# F4AIR.net
KiCad netlist of a schematic drawn in Altium Designer
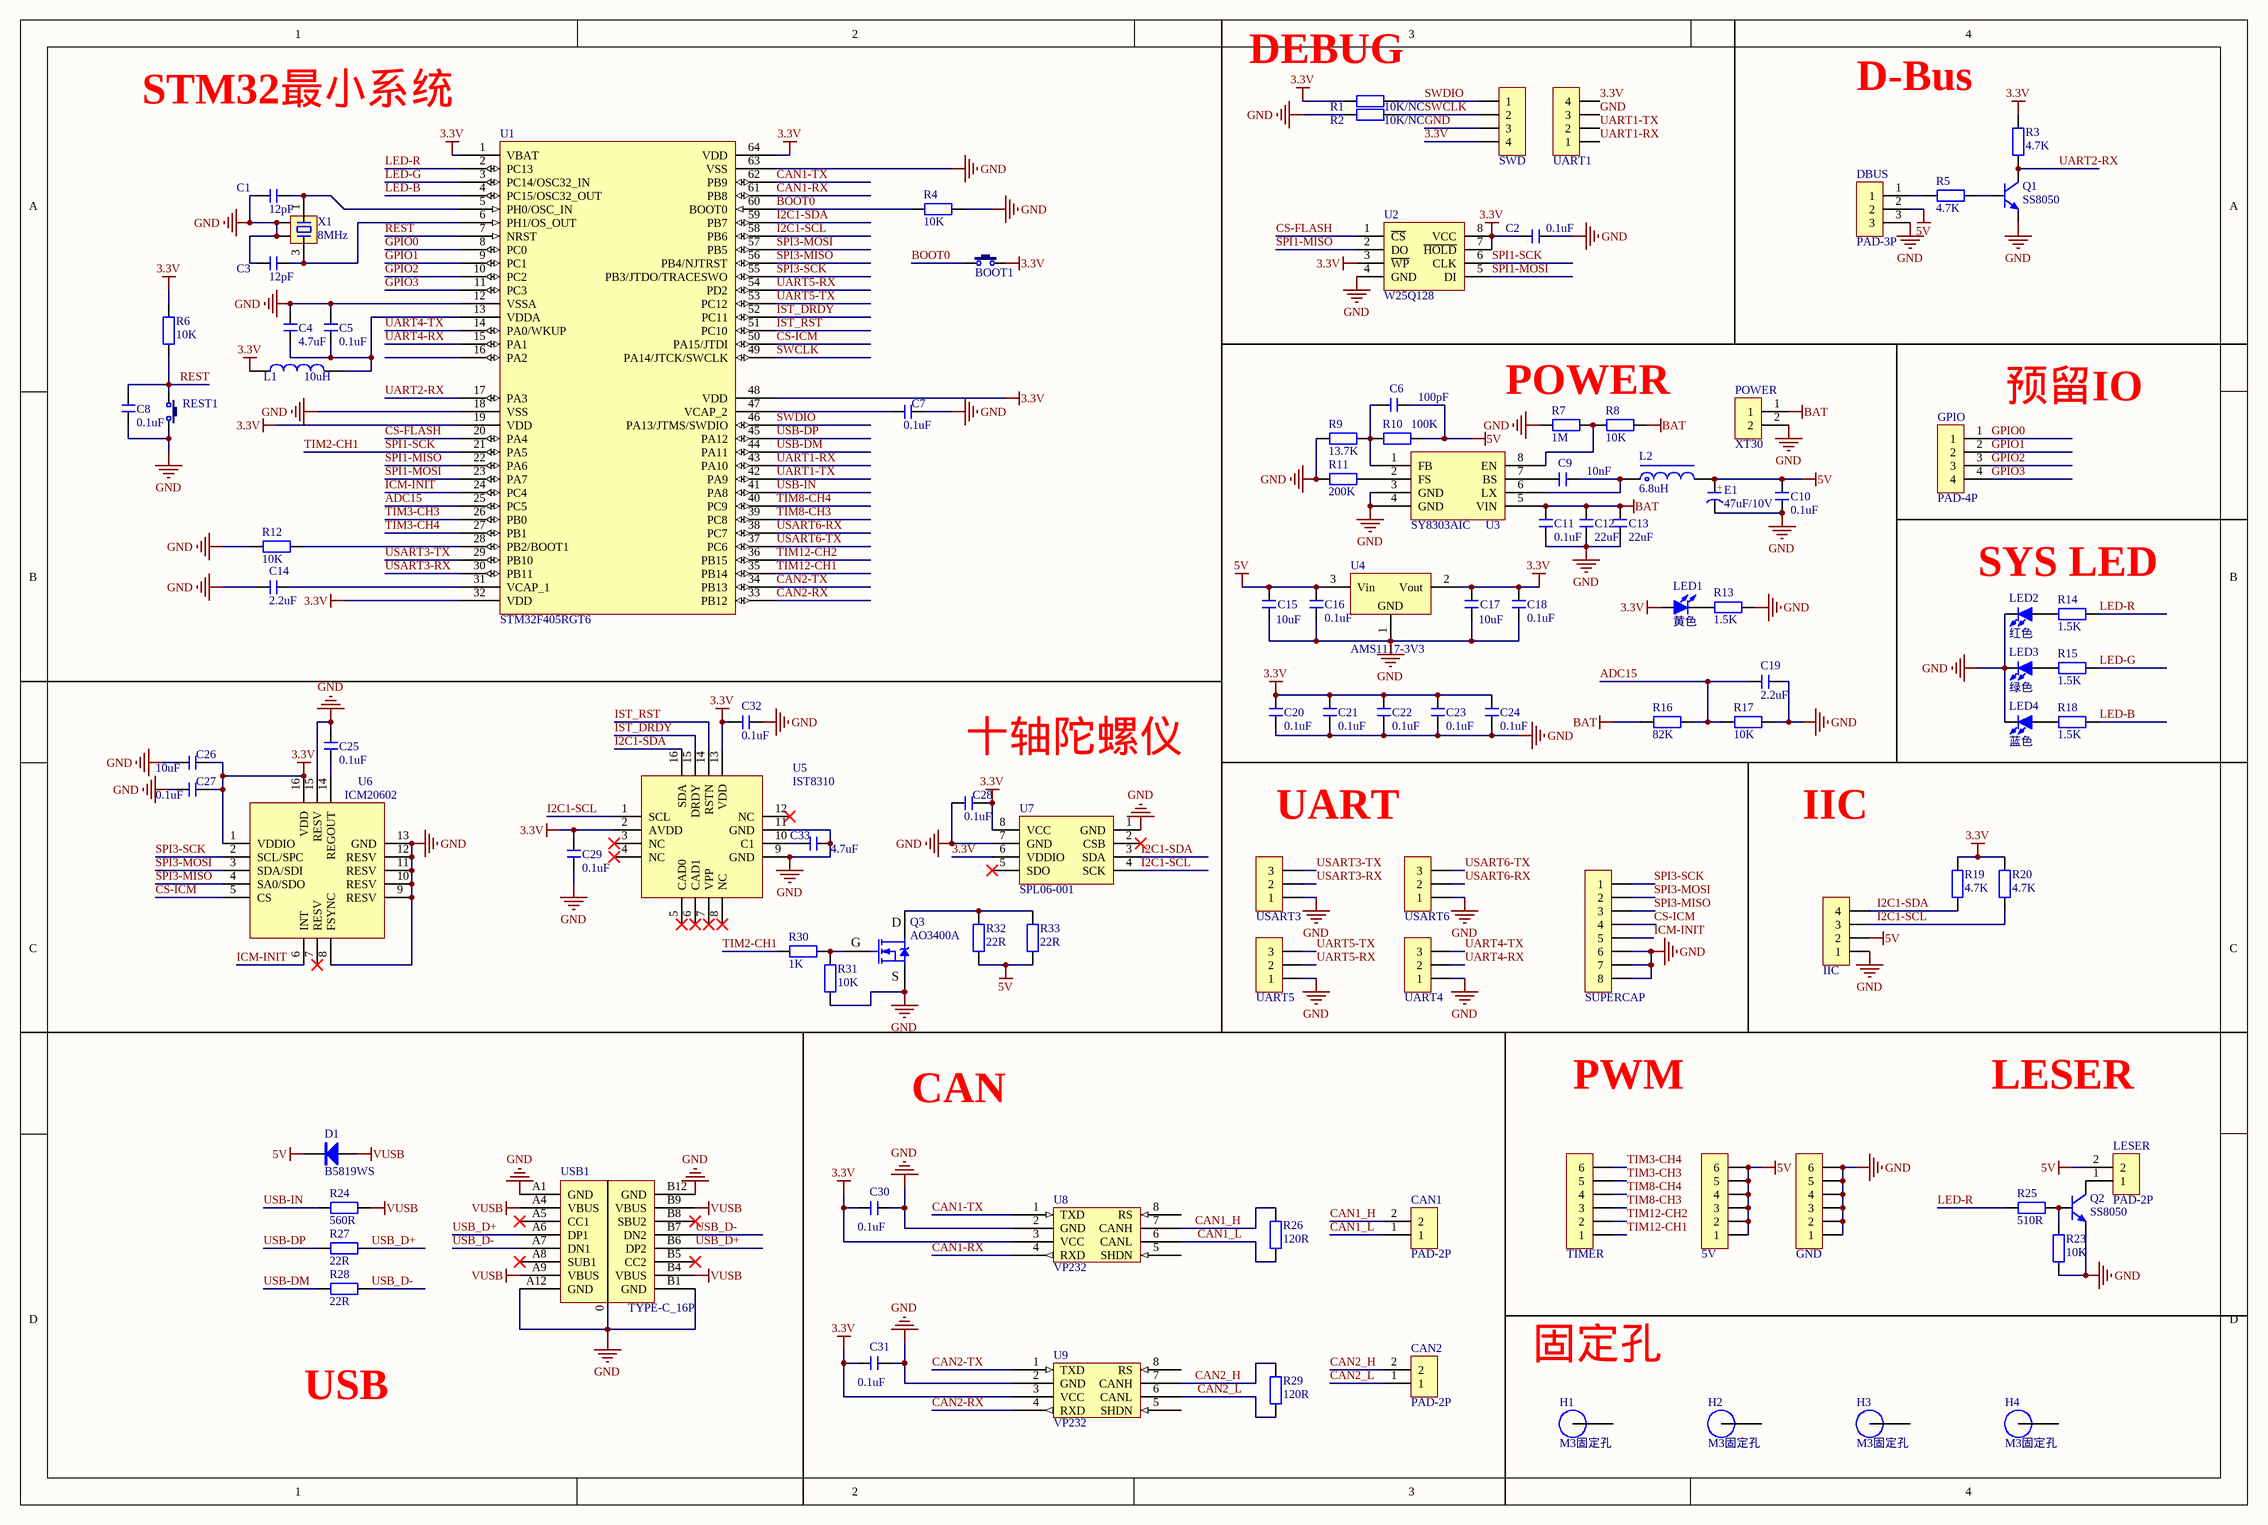
[diagram p0: F4AIR.SchDoc]

(export (version "E")
  (design (tool "Eeschema 10.0.6"))
  (components
    (comp (ref "5V")
      (value "HDR-1X6")
      (footprint "HDR2.54-LI-6P")
      (description "6P接插件")
      (libsource (lib "*") (part "Header 6"))
    )
    (comp (ref "BOOT1")
      (value "3x6x5")
      (footprint "TSW SMD-3*6*5")
      (description "3x6轻触开关")
      (libsource (lib "") (part "TSW 3x6_1"))
    )
    (comp (ref "C1")
      (value "12pF")
      (footprint "C 0603_M")
      (description "无极性贴片电容")
      (libsource (lib "Schlib1") (part "C"))
    )
    (comp (ref "C2")
      (value "0.1uF")
      (footprint "C 0603_M")
      (description "无极性贴片电容")
      (libsource (lib "Schlib") (part "C"))
    )
    (comp (ref "C3")
      (value "12pF")
      (footprint "C 0603_M")
      (description "无极性贴片电容")
      (libsource (lib "Schlib1") (part "C"))
    )
    (comp (ref "C4")
      (value "4.7uF")
      (footprint "C 0603_M")
      (description "无极性贴片电容")
      (libsource (lib "Schlib1") (part "C"))
    )
    (comp (ref "C5")
      (value "0.1uF")
      (footprint "C 0603_M")
      (description "无极性贴片电容")
      (libsource (lib "Schlib1") (part "C"))
    )
    (comp (ref "C6")
      (value "100pF")
      (footprint "C 0603_M")
      (description "无极性贴片电容")
      (libsource (lib "Schlib1") (part "C"))
    )
    (comp (ref "C7")
      (value "0.1uF")
      (footprint "C 0603_M")
      (description "无极性贴片电容")
      (libsource (lib "Schlib1") (part "C"))
    )
    (comp (ref "C8")
      (value "0.1uF")
      (footprint "C 0603_M")
      (description "无极性贴片电容")
      (libsource (lib "Schlib1") (part "C"))
    )
    (comp (ref "C9")
      (value "10nF")
      (footprint "C 0603_M")
      (description "无极性贴片电容")
      (libsource (lib "Schlib1") (part "C"))
    )
    (comp (ref "C10")
      (value "0.1uF")
      (footprint "C 0603_M")
      (description "无极性贴片电容")
      (libsource (lib "Schlib1") (part "C"))
    )
    (comp (ref "C11")
      (value "0.1uF")
      (footprint "C 0603_M")
      (description "无极性贴片电容")
      (libsource (lib "Schlib1") (part "C"))
    )
    (comp (ref "C12")
      (value "22uF")
      (footprint "C 1210_M")
      (description "无极性贴片电容")
      (libsource (lib "核心板v2") (part "C"))
    )
    (comp (ref "C13")
      (value "22uF")
      (footprint "C 1210_M")
      (description "无极性贴片电容")
      (libsource (lib "核心板v2") (part "C"))
    )
    (comp (ref "C14")
      (value "2.2uF")
      (footprint "C 0603_M")
      (description "无极性贴片电容")
      (libsource (lib "Schlib1") (part "C"))
    )
    (comp (ref "C15")
      (value "10uF")
      (footprint "C 0805_M")
      (description "无极性贴片电容")
      (libsource (lib "altium-import") (part "root_1_C_"))
    )
    (comp (ref "C16")
      (value "0.1uF")
      (footprint "C 0603_M")
      (description "无极性贴片电容")
      (libsource (lib "Schlib1") (part "C"))
    )
    (comp (ref "C17")
      (value "10uF")
      (footprint "C 0805_M")
      (description "无极性贴片电容")
      (libsource (lib "altium-import") (part "root_1_C_"))
    )
    (comp (ref "C18")
      (value "0.1uF")
      (footprint "C 0603_M")
      (description "无极性贴片电容")
      (libsource (lib "Schlib1") (part "C"))
    )
    (comp (ref "C19")
      (value "2.2uF")
      (footprint "C 0603_M")
      (description "无极性贴片电容")
      (libsource (lib "Schlib") (part "C"))
    )
    (comp (ref "C20")
      (value "0.1uF")
      (footprint "C 0603_M")
      (description "无极性贴片电容")
      (libsource (lib "Schlib1") (part "C"))
    )
    (comp (ref "C21")
      (value "0.1uF")
      (footprint "C 0603_M")
      (description "无极性贴片电容")
      (libsource (lib "Schlib1") (part "C"))
    )
    (comp (ref "C22")
      (value "0.1uF")
      (footprint "C 0603_M")
      (description "无极性贴片电容")
      (libsource (lib "Schlib1") (part "C"))
    )
    (comp (ref "C23")
      (value "0.1uF")
      (footprint "C 0603_M")
      (description "无极性贴片电容")
      (libsource (lib "Schlib1") (part "C"))
    )
    (comp (ref "C24")
      (value "0.1uF")
      (footprint "C 0603_M")
      (description "无极性贴片电容")
      (libsource (lib "Schlib1") (part "C"))
    )
    (comp (ref "C25")
      (value "0.1uF")
      (footprint "C 0603_M")
      (description "无极性贴片电容")
      (libsource (lib "Schlib1") (part "C"))
    )
    (comp (ref "C26")
      (value "10uF")
      (footprint "C 0805_M")
      (description "无极性贴片电容")
      (libsource (lib "Schlib1") (part "C"))
    )
    (comp (ref "C27")
      (value "0.1uF")
      (footprint "C 0603_M")
      (description "无极性贴片电容")
      (libsource (lib "Schlib1") (part "C"))
    )
    (comp (ref "C28")
      (value "0.1uF")
      (footprint "C 0603_M")
      (description "无极性贴片电容")
      (libsource (lib "Schlib1") (part "C"))
    )
    (comp (ref "C29")
      (value "0.1uF")
      (footprint "C 0603_M")
      (description "无极性贴片电容")
      (libsource (lib "Schlib1") (part "C"))
    )
    (comp (ref "C30")
      (value "0.1uF")
      (footprint "C 0603_M")
      (description "无极性贴片电容")
      (libsource (lib "Schlib1") (part "C"))
    )
    (comp (ref "C31")
      (value "0.1uF")
      (footprint "C 0603_M")
      (description "无极性贴片电容")
      (libsource (lib "Schlib1") (part "C"))
    )
    (comp (ref "C32")
      (value "0.1uF")
      (footprint "C 0603_M")
      (description "无极性贴片电容")
      (libsource (lib "Schlib1") (part "C"))
    )
    (comp (ref "C33")
      (value "4.7uF")
      (footprint "C 0603_M")
      (description "无极性贴片电容")
      (libsource (lib "Schlib1") (part "C"))
    )
    (comp (ref "CAN1") (value "PAD-2P") (footprint "MX 1.25-WS-2P") (libsource (lib "") (part "PAD-2P_1")))
    (comp (ref "CAN2") (value "PAD-2P") (footprint "MX 1.25-WS-2P") (libsource (lib "") (part "PAD-2P_1")))
    (comp (ref "D1")
      (value "B5819WS")
      (footprint "SOD-323")
      (description "肖特基二极管")
      (libsource (lib "Schlib") (part "SS54"))
    )
    (comp (ref "DBUS") (value "PAD-3P") (footprint "HDR2.54-WI-3P") (libsource (lib "F4AIR") (part "PAD-3P")))
    (comp (ref "E1")
      (value "47uF/10V")
      (footprint "CD A(3216)")
      (description "贴片钽电容")
      (libsource (lib "核心板v2") (part "C-CD"))
    )
    (comp (ref "GND")
      (value "HDR-1X6")
      (footprint "HDR2.54-LI-6P")
      (description "6P接插件")
      (libsource (lib "*") (part "Header 6"))
    )
    (comp (ref "GPIO") (value "PAD-4P") (footprint "PAD-1.25-4P") (libsource (lib "F4AIR") (part "PAD-4P")))
    (comp (ref "H1")
      (value "M3固定孔")
      (footprint "M3x4_N")
      (description "铜柱孔")
      (libsource (lib "F4AIR") (part "M3"))
    )
    (comp (ref "H2")
      (value "M3固定孔")
      (footprint "M3x4_N")
      (description "铜柱孔")
      (libsource (lib "F4AIR") (part "M3"))
    )
    (comp (ref "H3")
      (value "M3固定孔")
      (footprint "M3x4_N")
      (description "铜柱孔")
      (libsource (lib "F4AIR") (part "M3"))
    )
    (comp (ref "H4")
      (value "M3固定孔")
      (footprint "M3x4_N")
      (description "铜柱孔")
      (libsource (lib "F4AIR") (part "M3"))
    )
    (comp (ref "IIC")
      (value "HDR-1X4")
      (footprint "HDR2.54-LI-4P")
      (description "HDR 2.54 -4P")
      (libsource (lib "核心板v2") (part "HDR 2.54 -4P_1"))
    )
    (comp (ref "L1")
      (value "10uH")
      (footprint "L 0603")
      (description "小功率贴片电感")
      (libsource (lib "Schlib1") (part "L"))
    )
    (comp (ref "L2")
      (value "6.8uH")
      (footprint "L-SMD-0630")
      (description "贴片功率电感")
      (libsource (lib "核心板v2") (part "L-CD"))
    )
    (comp (ref "LED1")
      (value "黄色")
      (footprint "LED 0603Y")
      (description "贴片LED")
      (libsource (lib "核心板v2") (part "LED-SMD"))
    )
    (comp (ref "LED2")
      (value "红色")
      (footprint "LED 0603R")
      (description "贴片LED")
      (libsource (lib "核心板v2") (part "LED-SMD"))
    )
    (comp (ref "LED3")
      (value "绿色")
      (footprint "LED 0603G")
      (description "贴片LED")
      (libsource (lib "核心板v2") (part "LED-SMD"))
    )
    (comp (ref "LED4")
      (value "蓝色")
      (footprint "LED 0603B")
      (description "贴片LED")
      (libsource (lib "核心板v2") (part "LED-SMD"))
    )
    (comp (ref "LESER") (value "PAD-2P") (footprint "MX 1.25-WS-2P") (libsource (lib "") (part "PAD-2P_1")))
    (comp (ref "POWER") (value "XT30") (footprint "XT30-L") (libsource (lib "F4AIR") (part "PAD-2P")))
    (comp (ref "Q1")
      (value "SS8050")
      (footprint "SOT23-3M")
      (description "高频放大-NPN型")
      (libsource (lib "Schlib1") (part "8050-SMD"))
    )
    (comp (ref "Q2")
      (value "SS8050")
      (footprint "SOT23-3M")
      (description "高频放大-NPN型")
      (libsource (lib "核心板v2") (part "8050-SMD"))
    )
    (comp (ref "Q3") (value "AO3400A") (footprint "SOT23-3M") (libsource (lib "F4AIR") (part "AO3400A")))
    (comp (ref "R1")
      (value "10K/NC")
      (footprint "R 0603_M")
      (description "贴片电阻")
      (libsource (lib "Schlib1") (part "R"))
    )
    (comp (ref "R2")
      (value "10K/NC")
      (footprint "R 0603_M")
      (description "贴片电阻")
      (libsource (lib "Schlib1") (part "R"))
    )
    (comp (ref "R3")
      (value "4.7K")
      (footprint "R 0603_M")
      (description "贴片电阻")
      (libsource (lib "Schlib1") (part "R"))
    )
    (comp (ref "R4")
      (value "10K")
      (footprint "R 0603_M")
      (description "贴片电阻")
      (libsource (lib "Schlib1") (part "R"))
    )
    (comp (ref "R5")
      (value "4.7K")
      (footprint "R 0603_M")
      (description "贴片电阻")
      (libsource (lib "Schlib1") (part "R"))
    )
    (comp (ref "R6")
      (value "10K")
      (footprint "R 0603_M")
      (description "贴片电阻")
      (libsource (lib "Schlib1") (part "R"))
    )
    (comp (ref "R7")
      (value "1M")
      (footprint "R 0603_M")
      (description "贴片电阻")
      (libsource (lib "altium-import") (part "root_2_R_"))
    )
    (comp (ref "R8")
      (value "10K")
      (footprint "R 0603_M")
      (description "贴片电阻")
      (libsource (lib "altium-import") (part "root_2_R_"))
    )
    (comp (ref "R9")
      (value "13.7K")
      (footprint "R 0603_M")
      (description "贴片电阻")
      (libsource (lib "altium-import") (part "root_2_R_"))
    )
    (comp (ref "R10")
      (value "100K")
      (footprint "R 0603_M")
      (description "贴片电阻")
      (libsource (lib "altium-import") (part "root_2_R_"))
    )
    (comp (ref "R11")
      (value "200K")
      (footprint "R 0603_M")
      (description "贴片电阻")
      (libsource (lib "altium-import") (part "root_2_R_"))
    )
    (comp (ref "R12")
      (value "10K")
      (footprint "R 0603_M")
      (description "贴片电阻")
      (libsource (lib "Schlib1") (part "R"))
    )
    (comp (ref "R13")
      (value "1.5K")
      (footprint "R 0603_M")
      (description "贴片电阻")
      (libsource (lib "核心板v2") (part "R"))
    )
    (comp (ref "R14")
      (value "1.5K")
      (footprint "R 0603_M")
      (description "贴片电阻")
      (libsource (lib "核心板v2") (part "R"))
    )
    (comp (ref "R15")
      (value "1.5K")
      (footprint "R 0603_M")
      (description "贴片电阻")
      (libsource (lib "核心板v2") (part "R"))
    )
    (comp (ref "R16")
      (value "82K")
      (footprint "R 0603_M")
      (description "贴片电阻")
      (libsource (lib "Schlib") (part "R"))
    )
    (comp (ref "R17")
      (value "10K")
      (footprint "R 0603_M")
      (description "贴片电阻")
      (libsource (lib "Schlib") (part "R"))
    )
    (comp (ref "R18")
      (value "1.5K")
      (footprint "R 0603_M")
      (description "贴片电阻")
      (libsource (lib "核心板v2") (part "R"))
    )
    (comp (ref "R19")
      (value "4.7K")
      (footprint "R 0603_M")
      (description "贴片电阻")
      (libsource (lib "altium-import") (part "root_3_R_"))
    )
    (comp (ref "R20")
      (value "4.7K")
      (footprint "R 0603_M")
      (description "贴片电阻")
      (libsource (lib "altium-import") (part "root_1_R_"))
    )
    (comp (ref "R23")
      (value "10K")
      (footprint "R 0603_M")
      (description "贴片电阻")
      (libsource (lib "核心板v2") (part "R"))
    )
    (comp (ref "R24")
      (value "560R")
      (footprint "R 0603_M")
      (description "贴片电阻")
      (libsource (lib "Schlib1") (part "R"))
    )
    (comp (ref "R25")
      (value "510R")
      (footprint "R 0603_M")
      (description "贴片电阻")
      (libsource (lib "核心板v2") (part "R"))
    )
    (comp (ref "R26")
      (value "120R")
      (footprint "R 0603_M")
      (description "贴片电阻")
      (libsource (lib "altium-import") (part "root_1_R_"))
    )
    (comp (ref "R27")
      (value "22R")
      (footprint "R 0603_M")
      (description "贴片电阻")
      (libsource (lib "Schlib") (part "R"))
    )
    (comp (ref "R28")
      (value "22R")
      (footprint "R 0603_M")
      (description "贴片电阻")
      (libsource (lib "Schlib") (part "R"))
    )
    (comp (ref "R29")
      (value "120R")
      (footprint "R 0603_M")
      (description "贴片电阻")
      (libsource (lib "altium-import") (part "root_1_R_"))
    )
    (comp (ref "R30")
      (value "1K")
      (footprint "R 0603_M")
      (description "贴片电阻")
      (libsource (lib "F4AIR") (part "R"))
    )
    (comp (ref "R31")
      (value "10K")
      (footprint "R 0603_M")
      (description "贴片电阻")
      (libsource (lib "F4AIR") (part "R"))
    )
    (comp (ref "R32")
      (value "22R")
      (footprint "R 0603_M")
      (description "贴片电阻")
      (libsource (lib "F4AIR") (part "R"))
    )
    (comp (ref "R33")
      (value "22R")
      (footprint "R 0603_M")
      (description "贴片电阻")
      (libsource (lib "F4AIR") (part "R"))
    )
    (comp (ref "REST1")
      (value "3x6x5")
      (footprint "TSW SMD-3*6*5")
      (description "3x6轻触开关")
      (libsource (lib "Schlib1") (part "TSW 3x6"))
    )
    (comp (ref "SUPERCAP")
      (value "HDR-1X8")
      (footprint "MX 1.25-WS-6P")
      (description "HDR 2.54 -8P")
      (libsource (lib "cap") (part "HDR 2.54 -8P"))
    )
    (comp (ref "SWD")
      (value "HDR-1X4")
      (footprint "MX 1.25-WS-4P")
      (description "MX 1.25 -4P")
      (libsource (lib "Schlib1") (part "MX 1.25 -4P"))
    )
    (comp (ref "TIMER")
      (value "HDR-1X6")
      (footprint "HDR2.54-LI-6P")
      (description "6P接插件")
      (libsource (lib "*") (part "Header 6"))
    )
    (comp (ref "U1")
      (value "STM32F405RGT6")
      (footprint "LQFP64")
      (libsource (lib "Schlib") (part "STM32F405RGT6"))
    )
    (comp (ref "U2")
      (value "W25Q128")
      (footprint "SOP8_M - 208mil")
      (libsource (lib "Schlib") (part "W25Q128"))
    )
    (comp (ref "U3")
      (value "SY8303AIC")
      (footprint "SOT23-8")
      (description "DCDC降压芯片")
      (libsource (lib "核心板v2") (part "SY8303AIC"))
    )
    (comp (ref "U4")
      (value "AMS1117-3V3")
      (footprint "SOT-89")
      (description "三端稳压芯片")
      (libsource (lib "F4AIR") (part "AMS1117"))
    )
    (comp (ref "U5")
      (value "IST8310")
      (footprint "LGA16 3x3")
      (description "三轴电子罗盘")
      (libsource (lib "F4AIR") (part "IST8310"))
    )
    (comp (ref "U6") (value "ICM20602") (footprint "LGA16") (libsource (lib "Schlib1") (part "ICM20602")))
    (comp (ref "U7") (value "SPL06-001") (footprint "LGA08") (libsource (lib "Schlib1") (part "SPL06")))
    (comp (ref "U8")
      (value "VP232")
      (footprint "SOP8_M")
      (description "CAN芯片")
      (libsource (lib "核心板v2") (part "MAX3051EKA+T"))
    )
    (comp (ref "U9")
      (value "VP232")
      (footprint "SOP8_M")
      (description "CAN芯片")
      (libsource (lib "核心板v2") (part "MAX3051EKA+T"))
    )
    (comp (ref "UART1")
      (value "HDR-1X4")
      (footprint "MX 1.25-WS-4P")
      (description "HDR 2.54 -4P")
      (libsource (lib "核心板v2") (part "HDR 2.54 -4P_1"))
    )
    (comp (ref "UART4")
      (value "HDR-1X3")
      (footprint "MX 1.25-WS-3P")
      (description "HDR 2.54 -3P")
      (libsource (lib "Schlib1") (part "HDR 2.54 -3P"))
    )
    (comp (ref "UART5")
      (value "HDR-1X3")
      (footprint "MX 1.25-WS-3P")
      (description "HDR 2.54 -3P")
      (libsource (lib "Schlib1") (part "HDR 2.54 -3P"))
    )
    (comp (ref "USART3")
      (value "HDR-1X3")
      (footprint "MX 1.25-WS-3P")
      (description "HDR 2.54 -3P")
      (libsource (lib "Schlib1") (part "HDR 2.54 -3P"))
    )
    (comp (ref "USART6")
      (value "HDR-1X3")
      (footprint "MX 1.25-WS-3P")
      (description "HDR 2.54 -3P")
      (libsource (lib "Schlib1") (part "HDR 2.54 -3P"))
    )
    (comp (ref "USB1")
      (value "TYPE-C_16P")
      (footprint "Type-C_16p")
      (libsource (lib "Schlib") (part "TYPE-C_16P"))
    )
    (comp (ref "X1")
      (value "8MHz")
      (footprint "OSC 3225-4P")
      (description "4脚无源晶振")
      (libsource (lib "Schlib1") (part "XTAL-4P"))
    )
  )
  (nets
    (net (code "1") (name "/ADC15") (class "Default")
      (node (ref "C19") (pin "1") (pinfunction "1_1") (pintype "passive"))
      (node (ref "R16") (pin "2") (pinfunction "2_2") (pintype "passive"))
      (node (ref "R17") (pin "1") (pinfunction "1_1") (pintype "passive"))
      (node (ref "U1") (pin "25") (pinfunction "PC5_25") (pintype "bidirectional"))
    )
    (net (code "2") (name "/BOOT0") (class "Default")
      (node (ref "BOOT1") (pin "1") (pinfunction "1_1") (pintype "passive"))
      (node (ref "R4") (pin "1") (pinfunction "1_1") (pintype "passive"))
      (node (ref "U1") (pin "60") (pinfunction "BOOT0_60") (pintype "input"))
    )
    (net (code "3") (name "/CAN1-RX") (class "Default")
      (node (ref "U1") (pin "61") (pinfunction "PB8_61") (pintype "bidirectional"))
      (node (ref "U8") (pin "4") (pinfunction "RXD_4") (pintype "output"))
    )
    (net (code "4") (name "/CAN1-TX") (class "Default")
      (node (ref "U1") (pin "62") (pinfunction "PB9_62") (pintype "bidirectional"))
      (node (ref "U8") (pin "1") (pinfunction "TXD_1") (pintype "input"))
    )
    (net (code "5") (name "/CAN1_H") (class "Default")
      (node (ref "CAN1") (pin "2") (pinfunction "2_2") (pintype "passive"))
      (node (ref "R26") (pin "2") (pinfunction "2_2") (pintype "passive"))
      (node (ref "U8") (pin "7") (pinfunction "CANH_7") (pintype "passive"))
    )
    (net (code "6") (name "/CAN1_L") (class "Default")
      (node (ref "CAN1") (pin "1") (pinfunction "1_1") (pintype "passive"))
      (node (ref "R26") (pin "1") (pinfunction "1_1") (pintype "passive"))
      (node (ref "U8") (pin "6") (pinfunction "CANL_6") (pintype "passive"))
    )
    (net (code "7") (name "/CAN2-RX") (class "Default")
      (node (ref "U1") (pin "33") (pinfunction "PB12_33") (pintype "bidirectional"))
      (node (ref "U9") (pin "4") (pinfunction "RXD_4") (pintype "output"))
    )
    (net (code "8") (name "/CAN2-TX") (class "Default")
      (node (ref "U1") (pin "34") (pinfunction "PB13_34") (pintype "bidirectional"))
      (node (ref "U9") (pin "1") (pinfunction "TXD_1") (pintype "input"))
    )
    (net (code "9") (name "/CAN2_H") (class "Default")
      (node (ref "CAN2") (pin "2") (pinfunction "2_2") (pintype "passive"))
      (node (ref "R29") (pin "2") (pinfunction "2_2") (pintype "passive"))
      (node (ref "U9") (pin "7") (pinfunction "CANH_7") (pintype "passive"))
    )
    (net (code "10") (name "/CAN2_L") (class "Default")
      (node (ref "CAN2") (pin "1") (pinfunction "1_1") (pintype "passive"))
      (node (ref "R29") (pin "1") (pinfunction "1_1") (pintype "passive"))
      (node (ref "U9") (pin "6") (pinfunction "CANL_6") (pintype "passive"))
    )
    (net (code "11") (name "/CS-FLASH") (class "Default")
      (node (ref "U1") (pin "20") (pinfunction "PA4_20") (pintype "bidirectional"))
      (node (ref "U2") (pin "1") (pinfunction "~{CS}_1") (pintype "passive"))
    )
    (net (code "12") (name "/CS-ICM") (class "Default")
      (node (ref "SUPERCAP") (pin "4") (pinfunction "4_4") (pintype "passive"))
      (node (ref "U1") (pin "50") (pinfunction "PA15/JTDI_50") (pintype "bidirectional"))
      (node (ref "U6") (pin "5") (pinfunction "CS_5") (pintype "passive"))
    )
    (net (code "13") (name "/GPIO0") (class "Default")
      (node (ref "GPIO") (pin "1") (pinfunction "1_1") (pintype "passive"))
      (node (ref "U1") (pin "8") (pinfunction "PC0_8") (pintype "bidirectional"))
    )
    (net (code "14") (name "/GPIO1") (class "Default")
      (node (ref "GPIO") (pin "2") (pinfunction "2_2") (pintype "passive"))
      (node (ref "U1") (pin "9") (pinfunction "PC1_9") (pintype "bidirectional"))
    )
    (net (code "15") (name "/GPIO2") (class "Default")
      (node (ref "GPIO") (pin "3") (pinfunction "3_3") (pintype "passive"))
      (node (ref "U1") (pin "10") (pinfunction "PC2_10") (pintype "bidirectional"))
    )
    (net (code "16") (name "/GPIO3") (class "Default")
      (node (ref "GPIO") (pin "4") (pinfunction "4_4") (pintype "passive"))
      (node (ref "U1") (pin "11") (pinfunction "PC3_11") (pintype "bidirectional"))
    )
    (net (code "17") (name "/I2C1-SCL") (class "Default")
      (node (ref "IIC") (pin "3") (pinfunction "3_3") (pintype "passive"))
      (node (ref "R20") (pin "1") (pinfunction "1_1") (pintype "passive"))
      (node (ref "U1") (pin "58") (pinfunction "PB6_58") (pintype "bidirectional"))
      (node (ref "U5") (pin "1") (pinfunction "SCL_1") (pintype "passive"))
      (node (ref "U7") (pin "4") (pinfunction "SCK_4") (pintype "passive"))
    )
    (net (code "18") (name "/I2C1-SDA") (class "Default")
      (node (ref "IIC") (pin "4") (pinfunction "4_4") (pintype "passive"))
      (node (ref "R19") (pin "2") (pinfunction "2_2") (pintype "passive"))
      (node (ref "U1") (pin "59") (pinfunction "PB7_59") (pintype "bidirectional"))
      (node (ref "U5") (pin "16") (pinfunction "SDA_16") (pintype "passive"))
      (node (ref "U7") (pin "3") (pinfunction "SDA_3") (pintype "passive"))
    )
    (net (code "19") (name "/ICM-INIT") (class "Default")
      (node (ref "SUPERCAP") (pin "5") (pinfunction "5_5") (pintype "passive"))
      (node (ref "U1") (pin "24") (pinfunction "PC4_24") (pintype "bidirectional"))
      (node (ref "U6") (pin "6") (pinfunction "INT_6") (pintype "passive"))
    )
    (net (code "20") (name "/IST_DRDY") (class "Default")
      (node (ref "U1") (pin "52") (pinfunction "PC11_52") (pintype "bidirectional"))
      (node (ref "U5") (pin "15") (pinfunction "DRDY_15") (pintype "passive"))
    )
    (net (code "21") (name "/IST_RST") (class "Default")
      (node (ref "U1") (pin "51") (pinfunction "PC10_51") (pintype "bidirectional"))
      (node (ref "U5") (pin "14") (pinfunction "RSTN_14") (pintype "passive"))
    )
    (net (code "22") (name "/LED-B") (class "Default")
      (node (ref "R18") (pin "2") (pinfunction "2_2") (pintype "passive"))
      (node (ref "U1") (pin "4") (pinfunction "PC15/OSC32_OUT_4") (pintype "bidirectional"))
    )
    (net (code "23") (name "/LED-G") (class "Default")
      (node (ref "R15") (pin "2") (pinfunction "2_2") (pintype "passive"))
      (node (ref "U1") (pin "3") (pinfunction "PC14/OSC32_IN_3") (pintype "bidirectional"))
    )
    (net (code "24") (name "/LED-R") (class "Default")
      (node (ref "R14") (pin "2") (pinfunction "2_2") (pintype "passive"))
      (node (ref "R25") (pin "1") (pinfunction "1_1") (pintype "passive"))
      (node (ref "U1") (pin "2") (pinfunction "PC13_2") (pintype "bidirectional"))
    )
    (net (code "25") (name "/REST") (class "Default")
      (node (ref "C8") (pin "2") (pinfunction "2_2") (pintype "passive"))
      (node (ref "R6") (pin "1") (pinfunction "1_1") (pintype "passive"))
      (node (ref "REST1") (pin "1") (pinfunction "1_1") (pintype "passive"))
      (node (ref "U1") (pin "7") (pinfunction "NRST_7") (pintype "input"))
    )
    (net (code "26") (name "/SPI1-MISO") (class "Default")
      (node (ref "U1") (pin "22") (pinfunction "PA6_22") (pintype "bidirectional"))
      (node (ref "U2") (pin "2") (pinfunction "DO_2") (pintype "passive"))
    )
    (net (code "27") (name "/SPI1-MOSI") (class "Default")
      (node (ref "U1") (pin "23") (pinfunction "PA7_23") (pintype "bidirectional"))
      (node (ref "U2") (pin "5") (pinfunction "DI_5") (pintype "passive"))
    )
    (net (code "28") (name "/SPI1-SCK") (class "Default")
      (node (ref "R30") (pin "1") (pinfunction "1_1") (pintype "passive"))
      (node (ref "U1") (pin "21") (pinfunction "PA5_21") (pintype "bidirectional"))
      (node (ref "U2") (pin "6") (pinfunction "CLK_6") (pintype "passive"))
    )
    (net (code "29") (name "/SPI3-MISO") (class "Default")
      (node (ref "SUPERCAP") (pin "3") (pinfunction "3_3") (pintype "passive"))
      (node (ref "U1") (pin "56") (pinfunction "PB4/NJTRST_56") (pintype "bidirectional"))
      (node (ref "U6") (pin "4") (pinfunction "SA0/SDO_4") (pintype "passive"))
    )
    (net (code "30") (name "/SPI3-MOSI") (class "Default")
      (node (ref "SUPERCAP") (pin "2") (pinfunction "2_2") (pintype "passive"))
      (node (ref "U1") (pin "57") (pinfunction "PB5_57") (pintype "bidirectional"))
      (node (ref "U6") (pin "3") (pinfunction "SDA/SDI_3") (pintype "passive"))
    )
    (net (code "31") (name "/SPI3-SCK") (class "Default")
      (node (ref "SUPERCAP") (pin "1") (pinfunction "1_1") (pintype "passive"))
      (node (ref "U1") (pin "55") (pinfunction "PB3/JTDO/TRACESWO_55") (pintype "bidirectional"))
      (node (ref "U6") (pin "2") (pinfunction "SCL/SPC_2") (pintype "passive"))
    )
    (net (code "32") (name "/SWCLK") (class "Default")
      (node (ref "R2") (pin "2") (pinfunction "2_2") (pintype "passive"))
      (node (ref "SWD") (pin "2") (pinfunction "2_2") (pintype "passive"))
      (node (ref "U1") (pin "49") (pinfunction "PA14/JTCK/SWCLK_49") (pintype "bidirectional"))
    )
    (net (code "33") (name "/SWDIO") (class "Default")
      (node (ref "R1") (pin "2") (pinfunction "2_2") (pintype "passive"))
      (node (ref "SWD") (pin "1") (pinfunction "1_1") (pintype "passive"))
      (node (ref "U1") (pin "46") (pinfunction "PA13/JTMS/SWDIO_46") (pintype "bidirectional"))
    )
    (net (code "34") (name "/TIM3-CH3") (class "Default")
      (node (ref "TIMER") (pin "5") (pinfunction "5_5") (pintype "passive"))
      (node (ref "U1") (pin "26") (pinfunction "PB0_26") (pintype "bidirectional"))
    )
    (net (code "35") (name "/TIM3-CH4") (class "Default")
      (node (ref "TIMER") (pin "6") (pinfunction "6_6") (pintype "passive"))
      (node (ref "U1") (pin "27") (pinfunction "PB1_27") (pintype "bidirectional"))
    )
    (net (code "36") (name "/TIM8-CH3") (class "Default")
      (node (ref "TIMER") (pin "3") (pinfunction "3_3") (pintype "passive"))
      (node (ref "U1") (pin "39") (pinfunction "PC8_39") (pintype "bidirectional"))
    )
    (net (code "37") (name "/TIM8-CH4") (class "Default")
      (node (ref "TIMER") (pin "4") (pinfunction "4_4") (pintype "passive"))
      (node (ref "U1") (pin "40") (pinfunction "PC9_40") (pintype "bidirectional"))
    )
    (net (code "38") (name "/TIM12-CH1") (class "Default")
      (node (ref "TIMER") (pin "1") (pinfunction "1_1") (pintype "passive"))
      (node (ref "U1") (pin "35") (pinfunction "PB14_35") (pintype "bidirectional"))
    )
    (net (code "39") (name "/TIM12-CH2") (class "Default")
      (node (ref "TIMER") (pin "2") (pinfunction "2_2") (pintype "passive"))
      (node (ref "U1") (pin "36") (pinfunction "PB15_36") (pintype "bidirectional"))
    )
    (net (code "40") (name "/UART1-RX") (class "Default")
      (node (ref "U1") (pin "43") (pinfunction "PA10_43") (pintype "bidirectional"))
      (node (ref "UART1") (pin "1") (pinfunction "1_1") (pintype "passive"))
    )
    (net (code "41") (name "/UART1-TX") (class "Default")
      (node (ref "U1") (pin "42") (pinfunction "PA9_42") (pintype "bidirectional"))
      (node (ref "UART1") (pin "2") (pinfunction "2_2") (pintype "passive"))
    )
    (net (code "42") (name "/UART2-RX") (class "Default")
      (node (ref "Q1") (pin "3") (pinfunction "C_3") (pintype "passive"))
      (node (ref "R3") (pin "1") (pinfunction "1_1") (pintype "passive"))
      (node (ref "U1") (pin "17") (pinfunction "PA3_17") (pintype "bidirectional"))
    )
    (net (code "43") (name "/UART4-RX") (class "Default")
      (node (ref "U1") (pin "15") (pinfunction "PA1_15") (pintype "bidirectional"))
      (node (ref "UART4") (pin "2") (pinfunction "2_2") (pintype "passive"))
    )
    (net (code "44") (name "/UART4-TX") (class "Default")
      (node (ref "U1") (pin "14") (pinfunction "PA0/WKUP_14") (pintype "bidirectional"))
      (node (ref "UART4") (pin "3") (pinfunction "3_3") (pintype "passive"))
    )
    (net (code "45") (name "/UART5-RX") (class "Default")
      (node (ref "U1") (pin "54") (pinfunction "PD2_54") (pintype "bidirectional"))
      (node (ref "UART5") (pin "2") (pinfunction "2_2") (pintype "passive"))
    )
    (net (code "46") (name "/UART5-TX") (class "Default")
      (node (ref "U1") (pin "53") (pinfunction "PC12_53") (pintype "bidirectional"))
      (node (ref "UART5") (pin "3") (pinfunction "3_3") (pintype "passive"))
    )
    (net (code "47") (name "/USART3-RX") (class "Default")
      (node (ref "U1") (pin "30") (pinfunction "PB11_30") (pintype "bidirectional"))
      (node (ref "USART3") (pin "2") (pinfunction "2_2") (pintype "passive"))
    )
    (net (code "48") (name "/USART3-TX") (class "Default")
      (node (ref "U1") (pin "29") (pinfunction "PB10_29") (pintype "bidirectional"))
      (node (ref "USART3") (pin "3") (pinfunction "3_3") (pintype "passive"))
    )
    (net (code "49") (name "/USART6-RX") (class "Default")
      (node (ref "U1") (pin "38") (pinfunction "PC7_38") (pintype "bidirectional"))
      (node (ref "USART6") (pin "2") (pinfunction "2_2") (pintype "passive"))
    )
    (net (code "50") (name "/USART6-TX") (class "Default")
      (node (ref "U1") (pin "37") (pinfunction "PC6_37") (pintype "bidirectional"))
      (node (ref "USART6") (pin "3") (pinfunction "3_3") (pintype "passive"))
    )
    (net (code "51") (name "/USB-DM") (class "Default")
      (node (ref "R28") (pin "1") (pinfunction "1_1") (pintype "passive"))
      (node (ref "U1") (pin "44") (pinfunction "PA11_44") (pintype "bidirectional"))
    )
    (net (code "52") (name "/USB-DP") (class "Default")
      (node (ref "R27") (pin "1") (pinfunction "1_1") (pintype "passive"))
      (node (ref "U1") (pin "45") (pinfunction "PA12_45") (pintype "bidirectional"))
    )
    (net (code "53") (name "/USB-IN") (class "Default")
      (node (ref "R24") (pin "1") (pinfunction "1_1") (pintype "passive"))
      (node (ref "U1") (pin "41") (pinfunction "PA8_41") (pintype "bidirectional"))
    )
    (net (code "54") (name "/USB_D+") (class "Default")
      (node (ref "R27") (pin "2") (pinfunction "2_2") (pintype "passive"))
      (node (ref "USB1") (pin "A6") (pinfunction "DP1_A6") (pintype "passive"))
      (node (ref "USB1") (pin "B6") (pinfunction "DP2_B6") (pintype "passive"))
    )
    (net (code "55") (name "/USB_D-") (class "Default")
      (node (ref "R28") (pin "2") (pinfunction "2_2") (pintype "passive"))
      (node (ref "USB1") (pin "A7") (pinfunction "DN1_A7") (pintype "passive"))
      (node (ref "USB1") (pin "B7") (pinfunction "DN2_B7") (pintype "passive"))
    )
    (net (code "56") (name "3.3V") (class "Default")
      (node (ref "BOOT1") (pin "2") (pinfunction "2_2") (pintype "passive"))
      (node (ref "C17") (pin "2") (pinfunction "2_2") (pintype "passive"))
      (node (ref "C18") (pin "1") (pinfunction "1_1") (pintype "passive"))
      (node (ref "C2") (pin "1") (pinfunction "1_1") (pintype "passive"))
      (node (ref "C20") (pin "1") (pinfunction "1_1") (pintype "passive"))
      (node (ref "C21") (pin "1") (pinfunction "1_1") (pintype "passive"))
      (node (ref "C22") (pin "1") (pinfunction "1_1") (pintype "passive"))
      (node (ref "C23") (pin "1") (pinfunction "1_1") (pintype "passive"))
      (node (ref "C24") (pin "1") (pinfunction "1_1") (pintype "passive"))
      (node (ref "C26") (pin "2") (pinfunction "2_2") (pintype "passive"))
      (node (ref "C27") (pin "2") (pinfunction "2_2") (pintype "passive"))
      (node (ref "C28") (pin "2") (pinfunction "2_2") (pintype "passive"))
      (node (ref "C29") (pin "2") (pinfunction "2_2") (pintype "passive"))
      (node (ref "C30") (pin "2") (pinfunction "2_2") (pintype "passive"))
      (node (ref "C31") (pin "2") (pinfunction "2_2") (pintype "passive"))
      (node (ref "C32") (pin "2") (pinfunction "2_2") (pintype "passive"))
      (node (ref "L1") (pin "1") (pinfunction "1_1") (pintype "passive"))
      (node (ref "LED1") (pin "1") (pinfunction "A_1") (pintype "passive"))
      (node (ref "R1") (pin "1") (pinfunction "1_1") (pintype "passive"))
      (node (ref "R19") (pin "1") (pinfunction "1_1") (pintype "passive"))
      (node (ref "R20") (pin "2") (pinfunction "2_2") (pintype "passive"))
      (node (ref "R3") (pin "2") (pinfunction "2_2") (pintype "passive"))
      (node (ref "R6") (pin "2") (pinfunction "2_2") (pintype "passive"))
      (node (ref "SWD") (pin "4") (pinfunction "4_4") (pintype "passive"))
      (node (ref "U1") (pin "1") (pinfunction "VBAT_1") (pintype "power_in"))
      (node (ref "U1") (pin "19") (pinfunction "VDD_19") (pintype "power_in"))
      (node (ref "U1") (pin "32") (pinfunction "VDD_32") (pintype "power_in"))
      (node (ref "U1") (pin "48") (pinfunction "VDD_48") (pintype "power_in"))
      (node (ref "U1") (pin "64") (pinfunction "VDD_64") (pintype "power_in"))
      (node (ref "U2") (pin "3") (pinfunction "~{WP}_3") (pintype "passive"))
      (node (ref "U2") (pin "7") (pinfunction "~{HOLD}_7") (pintype "passive"))
      (node (ref "U2") (pin "8") (pinfunction "VCC_8") (pintype "passive"))
      (node (ref "U4") (pin "2") (pinfunction "Vout_2") (pintype "passive"))
      (node (ref "U5") (pin "13") (pinfunction "VDD_13") (pintype "passive"))
      (node (ref "U5") (pin "2") (pinfunction "AVDD_2") (pintype "passive"))
      (node (ref "U6") (pin "1") (pinfunction "VDDIO_1") (pintype "passive"))
      (node (ref "U6") (pin "16") (pinfunction "VDD_16") (pintype "passive"))
      (node (ref "U7") (pin "6") (pinfunction "VDDIO_6") (pintype "passive"))
      (node (ref "U7") (pin "8") (pinfunction "VCC_8") (pintype "passive"))
      (node (ref "U8") (pin "3") (pinfunction "VCC_3") (pintype "power_in"))
      (node (ref "U9") (pin "3") (pinfunction "VCC_3") (pintype "power_in"))
      (node (ref "UART1") (pin "4") (pinfunction "4_4") (pintype "passive"))
    )
    (net (code "57") (name "5V") (class "Default")
      (node (ref "5V") (pin "1") (pinfunction "1_1") (pintype "passive"))
      (node (ref "5V") (pin "2") (pinfunction "2_2") (pintype "passive"))
      (node (ref "5V") (pin "3") (pinfunction "3_3") (pintype "passive"))
      (node (ref "5V") (pin "4") (pinfunction "4_4") (pintype "passive"))
      (node (ref "5V") (pin "5") (pinfunction "5_5") (pintype "passive"))
      (node (ref "5V") (pin "6") (pinfunction "6_6") (pintype "passive"))
      (node (ref "C10") (pin "1") (pinfunction "1_1") (pintype "passive"))
      (node (ref "C15") (pin "2") (pinfunction "2_2") (pintype "passive"))
      (node (ref "C16") (pin "1") (pinfunction "1_1") (pintype "passive"))
      (node (ref "C6") (pin "1") (pinfunction "1_1") (pintype "passive"))
      (node (ref "D1") (pin "2") (pinfunction "K_2") (pintype "passive"))
      (node (ref "DBUS") (pin "2") (pinfunction "2_2") (pintype "passive"))
      (node (ref "E1") (pin "1") (pinfunction "A_1") (pintype "passive"))
      (node (ref "IIC") (pin "2") (pinfunction "2_2") (pintype "passive"))
      (node (ref "L2") (pin "2") (pinfunction "2_2") (pintype "passive"))
      (node (ref "LESER") (pin "2") (pinfunction "2_2") (pintype "passive"))
      (node (ref "R10") (pin "1") (pinfunction "1_1") (pintype "passive"))
      (node (ref "R32") (pin "1") (pinfunction "1_1") (pintype "passive"))
      (node (ref "R33") (pin "1") (pinfunction "1_1") (pintype "passive"))
      (node (ref "U4") (pin "3") (pinfunction "Vin_3") (pintype "passive"))
    )
    (net (code "58") (name "BAT") (class "Default")
      (node (ref "C11") (pin "1") (pinfunction "1_1") (pintype "passive"))
      (node (ref "C12") (pin "2") (pinfunction "2_2") (pintype "passive"))
      (node (ref "C13") (pin "2") (pinfunction "2_2") (pintype "passive"))
      (node (ref "POWER") (pin "1") (pinfunction "1_1") (pintype "passive"))
      (node (ref "R16") (pin "1") (pinfunction "1_1") (pintype "passive"))
      (node (ref "R8") (pin "1") (pinfunction "1_1") (pintype "passive"))
      (node (ref "U3") (pin "5") (pinfunction "VIN_5") (pintype "passive"))
    )
    (net (code "59") (name "GND") (class "Default")
      (node (ref "C1") (pin "1") (pinfunction "1_1") (pintype "passive"))
      (node (ref "C10") (pin "2") (pinfunction "2_2") (pintype "passive"))
      (node (ref "C11") (pin "2") (pinfunction "2_2") (pintype "passive"))
      (node (ref "C12") (pin "1") (pinfunction "1_1") (pintype "passive"))
      (node (ref "C13") (pin "1") (pinfunction "1_1") (pintype "passive"))
      (node (ref "C14") (pin "1") (pinfunction "1_1") (pintype "passive"))
      (node (ref "C15") (pin "1") (pinfunction "1_1") (pintype "passive"))
      (node (ref "C16") (pin "2") (pinfunction "2_2") (pintype "passive"))
      (node (ref "C17") (pin "1") (pinfunction "1_1") (pintype "passive"))
      (node (ref "C18") (pin "2") (pinfunction "2_2") (pintype "passive"))
      (node (ref "C19") (pin "2") (pinfunction "2_2") (pintype "passive"))
      (node (ref "C2") (pin "2") (pinfunction "2_2") (pintype "passive"))
      (node (ref "C20") (pin "2") (pinfunction "2_2") (pintype "passive"))
      (node (ref "C21") (pin "2") (pinfunction "2_2") (pintype "passive"))
      (node (ref "C22") (pin "2") (pinfunction "2_2") (pintype "passive"))
      (node (ref "C23") (pin "2") (pinfunction "2_2") (pintype "passive"))
      (node (ref "C24") (pin "2") (pinfunction "2_2") (pintype "passive"))
      (node (ref "C25") (pin "2") (pinfunction "2_2") (pintype "passive"))
      (node (ref "C26") (pin "1") (pinfunction "1_1") (pintype "passive"))
      (node (ref "C27") (pin "1") (pinfunction "1_1") (pintype "passive"))
      (node (ref "C28") (pin "1") (pinfunction "1_1") (pintype "passive"))
      (node (ref "C29") (pin "1") (pinfunction "1_1") (pintype "passive"))
      (node (ref "C3") (pin "1") (pinfunction "1_1") (pintype "passive"))
      (node (ref "C30") (pin "1") (pinfunction "1_1") (pintype "passive"))
      (node (ref "C31") (pin "1") (pinfunction "1_1") (pintype "passive"))
      (node (ref "C32") (pin "1") (pinfunction "1_1") (pintype "passive"))
      (node (ref "C33") (pin "1") (pinfunction "1_1") (pintype "passive"))
      (node (ref "C4") (pin "2") (pinfunction "2_2") (pintype "passive"))
      (node (ref "C5") (pin "2") (pinfunction "2_2") (pintype "passive"))
      (node (ref "C7") (pin "2") (pinfunction "2_2") (pintype "passive"))
      (node (ref "C8") (pin "1") (pinfunction "1_1") (pintype "passive"))
      (node (ref "DBUS") (pin "3") (pinfunction "3_3") (pintype "passive"))
      (node (ref "E1") (pin "2") (pinfunction "K_2") (pintype "passive"))
      (node (ref "GND") (pin "1") (pinfunction "1_1") (pintype "passive"))
      (node (ref "GND") (pin "2") (pinfunction "2_2") (pintype "passive"))
      (node (ref "GND") (pin "3") (pinfunction "3_3") (pintype "passive"))
      (node (ref "GND") (pin "4") (pinfunction "4_4") (pintype "passive"))
      (node (ref "GND") (pin "5") (pinfunction "5_5") (pintype "passive"))
      (node (ref "GND") (pin "6") (pinfunction "6_6") (pintype "passive"))
      (node (ref "IIC") (pin "1") (pinfunction "1_1") (pintype "passive"))
      (node (ref "LED2") (pin "2") (pinfunction "K_2") (pintype "passive"))
      (node (ref "LED3") (pin "2") (pinfunction "K_2") (pintype "passive"))
      (node (ref "LED4") (pin "2") (pinfunction "K_2") (pintype "passive"))
      (node (ref "POWER") (pin "2") (pinfunction "2_2") (pintype "passive"))
      (node (ref "Q1") (pin "2") (pinfunction "E_2") (pintype "passive"))
      (node (ref "Q2") (pin "2") (pinfunction "E_2") (pintype "passive"))
      (node (ref "Q3") (pin "2") (pinfunction "S_2") (pintype "passive"))
      (node (ref "R11") (pin "2") (pinfunction "2_2") (pintype "passive"))
      (node (ref "R12") (pin "1") (pinfunction "1_1") (pintype "passive"))
      (node (ref "R13") (pin "2") (pinfunction "2_2") (pintype "passive"))
      (node (ref "R17") (pin "2") (pinfunction "2_2") (pintype "passive"))
      (node (ref "R2") (pin "1") (pinfunction "1_1") (pintype "passive"))
      (node (ref "R23") (pin "1") (pinfunction "1_1") (pintype "passive"))
      (node (ref "R31") (pin "1") (pinfunction "1_1") (pintype "passive"))
      (node (ref "R4") (pin "2") (pinfunction "2_2") (pintype "passive"))
      (node (ref "R7") (pin "2") (pinfunction "2_2") (pintype "passive"))
      (node (ref "R9") (pin "2") (pinfunction "2_2") (pintype "passive"))
      (node (ref "REST1") (pin "2") (pinfunction "2_2") (pintype "passive"))
      (node (ref "SUPERCAP") (pin "6") (pinfunction "6_6") (pintype "passive"))
      (node (ref "SUPERCAP") (pin "7") (pinfunction "7_7") (pintype "passive"))
      (node (ref "SUPERCAP") (pin "8") (pinfunction "8_8") (pintype "passive"))
      (node (ref "SWD") (pin "3") (pinfunction "3_3") (pintype "passive"))
      (node (ref "U1") (pin "12") (pinfunction "VSSA_12") (pintype "power_in"))
      (node (ref "U1") (pin "18") (pinfunction "VSS_18") (pintype "power_in"))
      (node (ref "U1") (pin "63") (pinfunction "VSS_63") (pintype "power_in"))
      (node (ref "U2") (pin "4") (pinfunction "GND_4") (pintype "passive"))
      (node (ref "U3") (pin "3") (pinfunction "GND_3") (pintype "passive"))
      (node (ref "U3") (pin "4") (pinfunction "GND_4") (pintype "passive"))
      (node (ref "U4") (pin "1") (pinfunction "GND_1") (pintype "passive"))
      (node (ref "U5") (pin "11") (pinfunction "GND_11") (pintype "passive"))
      (node (ref "U5") (pin "9") (pinfunction "GND_9") (pintype "passive"))
      (node (ref "U6") (pin "10") (pinfunction "RESV_10") (pintype "passive"))
      (node (ref "U6") (pin "11") (pinfunction "RESV_11") (pintype "passive"))
      (node (ref "U6") (pin "12") (pinfunction "RESV_12") (pintype "passive"))
      (node (ref "U6") (pin "13") (pinfunction "GND_13") (pintype "passive"))
      (node (ref "U6") (pin "15") (pinfunction "RESV_15") (pintype "passive"))
      (node (ref "U6") (pin "8") (pinfunction "FSYNC_8") (pintype "passive"))
      (node (ref "U6") (pin "9") (pinfunction "RESV_9") (pintype "passive"))
      (node (ref "U7") (pin "1") (pinfunction "GND_1") (pintype "passive"))
      (node (ref "U7") (pin "7") (pinfunction "GND_7") (pintype "passive"))
      (node (ref "U8") (pin "2") (pinfunction "GND_2") (pintype "power_in"))
      (node (ref "U9") (pin "2") (pinfunction "GND_2") (pintype "power_in"))
      (node (ref "UART1") (pin "3") (pinfunction "3_3") (pintype "passive"))
      (node (ref "UART4") (pin "1") (pinfunction "1_1") (pintype "passive"))
      (node (ref "UART5") (pin "1") (pinfunction "1_1") (pintype "passive"))
      (node (ref "USART3") (pin "1") (pinfunction "1_1") (pintype "passive"))
      (node (ref "USART6") (pin "1") (pinfunction "1_1") (pintype "passive"))
      (node (ref "USB1") (pin "0") (pinfunction "0_0") (pintype "passive"))
      (node (ref "USB1") (pin "A1") (pinfunction "GND_A1") (pintype "passive"))
      (node (ref "USB1") (pin "A12") (pinfunction "GND_A12") (pintype "passive"))
      (node (ref "USB1") (pin "B1") (pinfunction "GND_B1") (pintype "passive"))
      (node (ref "USB1") (pin "B12") (pinfunction "GND_B12") (pintype "passive"))
      (node (ref "X1") (pin "2") (pinfunction "2_2") (pintype "passive"))
      (node (ref "X1") (pin "4") (pinfunction "4_4") (pintype "passive"))
    )
    (net (code "60") (name "Net-(DBUS-Pad1)") (class "Default")
      (node (ref "DBUS") (pin "1") (pinfunction "1_1") (pintype "passive"))
      (node (ref "R5") (pin "1") (pinfunction "1_1") (pintype "passive"))
    )
    (net (code "61") (name "Net-(LED1-K)") (class "Default")
      (node (ref "LED1") (pin "2") (pinfunction "K_2") (pintype "passive"))
      (node (ref "R13") (pin "1") (pinfunction "1_1") (pintype "passive"))
    )
    (net (code "62") (name "Net-(LED2-A)") (class "Default")
      (node (ref "LED2") (pin "1") (pinfunction "A_1") (pintype "passive"))
      (node (ref "R14") (pin "1") (pinfunction "1_1") (pintype "passive"))
    )
    (net (code "63") (name "Net-(LED3-A)") (class "Default")
      (node (ref "LED3") (pin "1") (pinfunction "A_1") (pintype "passive"))
      (node (ref "R15") (pin "1") (pinfunction "1_1") (pintype "passive"))
    )
    (net (code "64") (name "Net-(LED4-A)") (class "Default")
      (node (ref "LED4") (pin "1") (pinfunction "A_1") (pintype "passive"))
      (node (ref "R18") (pin "1") (pinfunction "1_1") (pintype "passive"))
    )
    (net (code "65") (name "Net-(Q1-B)") (class "Default")
      (node (ref "Q1") (pin "1") (pinfunction "B_1") (pintype "passive"))
      (node (ref "R5") (pin "2") (pinfunction "2_2") (pintype "passive"))
    )
    (net (code "66") (name "Net-(Q2-B)") (class "Default")
      (node (ref "Q2") (pin "1") (pinfunction "B_1") (pintype "passive"))
      (node (ref "R23") (pin "2") (pinfunction "2_2") (pintype "passive"))
      (node (ref "R25") (pin "2") (pinfunction "2_2") (pintype "passive"))
    )
    (net (code "67") (name "Net-(Q2-C)") (class "Default")
      (node (ref "LESER") (pin "1") (pinfunction "1_1") (pintype "passive"))
      (node (ref "Q2") (pin "3") (pinfunction "C_3") (pintype "passive"))
    )
    (net (code "68") (name "Net-(Q3-D)") (class "Default")
      (node (ref "Q3") (pin "3") (pinfunction "D_3") (pintype "passive"))
      (node (ref "R32") (pin "2") (pinfunction "2_2") (pintype "passive"))
      (node (ref "R33") (pin "2") (pinfunction "2_2") (pintype "passive"))
    )
    (net (code "69") (name "Net-(Q3-G)") (class "Default")
      (node (ref "Q3") (pin "1") (pinfunction "G_1") (pintype "passive"))
      (node (ref "R30") (pin "2") (pinfunction "2_2") (pintype "passive"))
      (node (ref "R31") (pin "2") (pinfunction "2_2") (pintype "passive"))
    )
    (net (code "70") (name "Net-(U1-PB2{slash}BOOT1)") (class "Default")
      (node (ref "R12") (pin "2") (pinfunction "2_2") (pintype "passive"))
      (node (ref "U1") (pin "28") (pinfunction "PB2/BOOT1_28") (pintype "bidirectional"))
    )
    (net (code "71") (name "Net-(U1-PH0{slash}OSC_IN)") (class "Default")
      (node (ref "C1") (pin "2") (pinfunction "2_2") (pintype "passive"))
      (node (ref "U1") (pin "5") (pinfunction "PH0/OSC_IN_5") (pintype "input"))
      (node (ref "X1") (pin "1") (pinfunction "1_1") (pintype "passive"))
    )
    (net (code "72") (name "Net-(U1-PH1{slash}OS_OUT)") (class "Default")
      (node (ref "C3") (pin "2") (pinfunction "2_2") (pintype "passive"))
      (node (ref "U1") (pin "6") (pinfunction "PH1/OS_OUT_6") (pintype "input"))
      (node (ref "X1") (pin "3") (pinfunction "3_3") (pintype "passive"))
    )
    (net (code "73") (name "Net-(U1-VCAP_1)") (class "Default")
      (node (ref "C14") (pin "2") (pinfunction "2_2") (pintype "passive"))
      (node (ref "U1") (pin "31") (pinfunction "VCAP_1_31") (pintype "passive"))
    )
    (net (code "74") (name "Net-(U1-VCAP_2)") (class "Default")
      (node (ref "C7") (pin "1") (pinfunction "1_1") (pintype "passive"))
      (node (ref "U1") (pin "47") (pinfunction "VCAP_2_47") (pintype "passive"))
    )
    (net (code "75") (name "Net-(U1-VDDA)") (class "Default")
      (node (ref "C4") (pin "1") (pinfunction "1_1") (pintype "passive"))
      (node (ref "C5") (pin "1") (pinfunction "1_1") (pintype "passive"))
      (node (ref "L1") (pin "2") (pinfunction "2_2") (pintype "passive"))
      (node (ref "U1") (pin "13") (pinfunction "VDDA_13") (pintype "power_in"))
    )
    (net (code "76") (name "Net-(U3-BS)") (class "Default")
      (node (ref "C9") (pin "2") (pinfunction "2_2") (pintype "passive"))
      (node (ref "U3") (pin "7") (pinfunction "BS_7") (pintype "passive"))
    )
    (net (code "77") (name "Net-(U3-EN)") (class "Default")
      (node (ref "R7") (pin "1") (pinfunction "1_1") (pintype "passive"))
      (node (ref "R8") (pin "2") (pinfunction "2_2") (pintype "passive"))
      (node (ref "U3") (pin "8") (pinfunction "EN_8") (pintype "passive"))
    )
    (net (code "78") (name "Net-(U3-FB)") (class "Default")
      (node (ref "C6") (pin "2") (pinfunction "2_2") (pintype "passive"))
      (node (ref "R10") (pin "2") (pinfunction "2_2") (pintype "passive"))
      (node (ref "R9") (pin "1") (pinfunction "1_1") (pintype "passive"))
      (node (ref "U3") (pin "1") (pinfunction "FB_1") (pintype "passive"))
    )
    (net (code "79") (name "Net-(U3-FS)") (class "Default")
      (node (ref "R11") (pin "1") (pinfunction "1_1") (pintype "passive"))
      (node (ref "U3") (pin "2") (pinfunction "FS_2") (pintype "passive"))
    )
    (net (code "80") (name "Net-(U3-LX)") (class "Default")
      (node (ref "C9") (pin "1") (pinfunction "1_1") (pintype "passive"))
      (node (ref "L2") (pin "1") (pinfunction "1_1") (pintype "passive"))
      (node (ref "U3") (pin "6") (pinfunction "LX_6") (pintype "passive"))
    )
    (net (code "81") (name "Net-(U5-C1)") (class "Default")
      (node (ref "C33") (pin "2") (pinfunction "2_2") (pintype "passive"))
      (node (ref "U5") (pin "10") (pinfunction "C1_10") (pintype "passive"))
    )
    (net (code "82") (name "Net-(U6-REGOUT)") (class "Default")
      (node (ref "C25") (pin "1") (pinfunction "1_1") (pintype "passive"))
      (node (ref "U6") (pin "14") (pinfunction "REGOUT_14") (pintype "passive"))
    )
    (net (code "83") (name "VUSB") (class "Default")
      (node (ref "D1") (pin "1") (pinfunction "A_1") (pintype "passive"))
      (node (ref "R24") (pin "2") (pinfunction "2_2") (pintype "passive"))
      (node (ref "USB1") (pin "A4") (pinfunction "VBUS_A4") (pintype "passive"))
      (node (ref "USB1") (pin "A9") (pinfunction "VBUS_A9") (pintype "passive"))
      (node (ref "USB1") (pin "B4") (pinfunction "VBUS_B4") (pintype "passive"))
      (node (ref "USB1") (pin "B9") (pinfunction "VBUS_B9") (pintype "passive"))
    )
    (net (code "84") (name "unconnected-(H1-Pad1)") (class "Default")
      (node (ref "H1") (pin "1") (pinfunction "1_1") (pintype "passive"))
    )
    (net (code "85") (name "unconnected-(H2-Pad1)") (class "Default")
      (node (ref "H2") (pin "1") (pinfunction "1_1") (pintype "passive"))
    )
    (net (code "86") (name "unconnected-(H3-Pad1)") (class "Default")
      (node (ref "H3") (pin "1") (pinfunction "1_1") (pintype "passive"))
    )
    (net (code "87") (name "unconnected-(H4-Pad1)") (class "Default")
      (node (ref "H4") (pin "1") (pinfunction "1_1") (pintype "passive"))
    )
    (net (code "88") (name "unconnected-(U1-PA2-Pad16)") (class "Default")
      (node (ref "U1") (pin "16") (pinfunction "PA2_16") (pintype "bidirectional"))
    )
    (net (code "89") (name "unconnected-(U5-CAD0-Pad5)") (class "Default")
      (node (ref "U5") (pin "5") (pinfunction "CAD0_5") (pintype "passive+no_connect"))
    )
    (net (code "90") (name "unconnected-(U5-CAD1-Pad6)") (class "Default")
      (node (ref "U5") (pin "6") (pinfunction "CAD1_6") (pintype "passive+no_connect"))
    )
    (net (code "91") (name "unconnected-(U5-NC-Pad3)") (class "Default")
      (node (ref "U5") (pin "3") (pinfunction "NC_3") (pintype "passive+no_connect"))
    )
    (net (code "92") (name "unconnected-(U5-NC-Pad4)") (class "Default")
      (node (ref "U5") (pin "4") (pinfunction "NC_4") (pintype "passive+no_connect"))
    )
    (net (code "93") (name "unconnected-(U5-NC-Pad8)") (class "Default")
      (node (ref "U5") (pin "8") (pinfunction "NC_8") (pintype "passive+no_connect"))
    )
    (net (code "94") (name "unconnected-(U5-NC-Pad12)") (class "Default")
      (node (ref "U5") (pin "12") (pinfunction "NC_12") (pintype "passive+no_connect"))
    )
    (net (code "95") (name "unconnected-(U5-VPP-Pad7)") (class "Default")
      (node (ref "U5") (pin "7") (pinfunction "VPP_7") (pintype "passive+no_connect"))
    )
    (net (code "96") (name "unconnected-(U6-RESV-Pad7)") (class "Default")
      (node (ref "U6") (pin "7") (pinfunction "RESV_7") (pintype "passive+no_connect"))
    )
    (net (code "97") (name "unconnected-(U7-CSB-Pad2)") (class "Default")
      (node (ref "U7") (pin "2") (pinfunction "CSB_2") (pintype "passive+no_connect"))
    )
    (net (code "98") (name "unconnected-(U7-SDO-Pad5)") (class "Default")
      (node (ref "U7") (pin "5") (pinfunction "SDO_5") (pintype "passive+no_connect"))
    )
    (net (code "99") (name "unconnected-(U8-RS-Pad8)") (class "Default")
      (node (ref "U8") (pin "8") (pinfunction "RS_8") (pintype "input"))
    )
    (net (code "100") (name "unconnected-(U8-SHDN-Pad5)") (class "Default")
      (node (ref "U8") (pin "5") (pinfunction "SHDN_5") (pintype "input"))
    )
    (net (code "101") (name "unconnected-(U9-RS-Pad8)") (class "Default")
      (node (ref "U9") (pin "8") (pinfunction "RS_8") (pintype "input"))
    )
    (net (code "102") (name "unconnected-(U9-SHDN-Pad5)") (class "Default")
      (node (ref "U9") (pin "5") (pinfunction "SHDN_5") (pintype "input"))
    )
    (net (code "103") (name "unconnected-(USB1-CC1-PadA5)") (class "Default")
      (node (ref "USB1") (pin "A5") (pinfunction "CC1_A5") (pintype "passive+no_connect"))
    )
    (net (code "104") (name "unconnected-(USB1-CC2-PadB5)") (class "Default")
      (node (ref "USB1") (pin "B5") (pinfunction "CC2_B5") (pintype "passive+no_connect"))
    )
    (net (code "105") (name "unconnected-(USB1-SBU2-PadB8)") (class "Default")
      (node (ref "USB1") (pin "B8") (pinfunction "SBU2_B8") (pintype "passive+no_connect"))
    )
    (net (code "106") (name "unconnected-(USB1-SUB1-PadA8)") (class "Default")
      (node (ref "USB1") (pin "A8") (pinfunction "SUB1_A8") (pintype "passive+no_connect"))
    )
  )
)
